# Arduino_DIY.net
KiCad netlist of a schematic drawn in Altium Designer
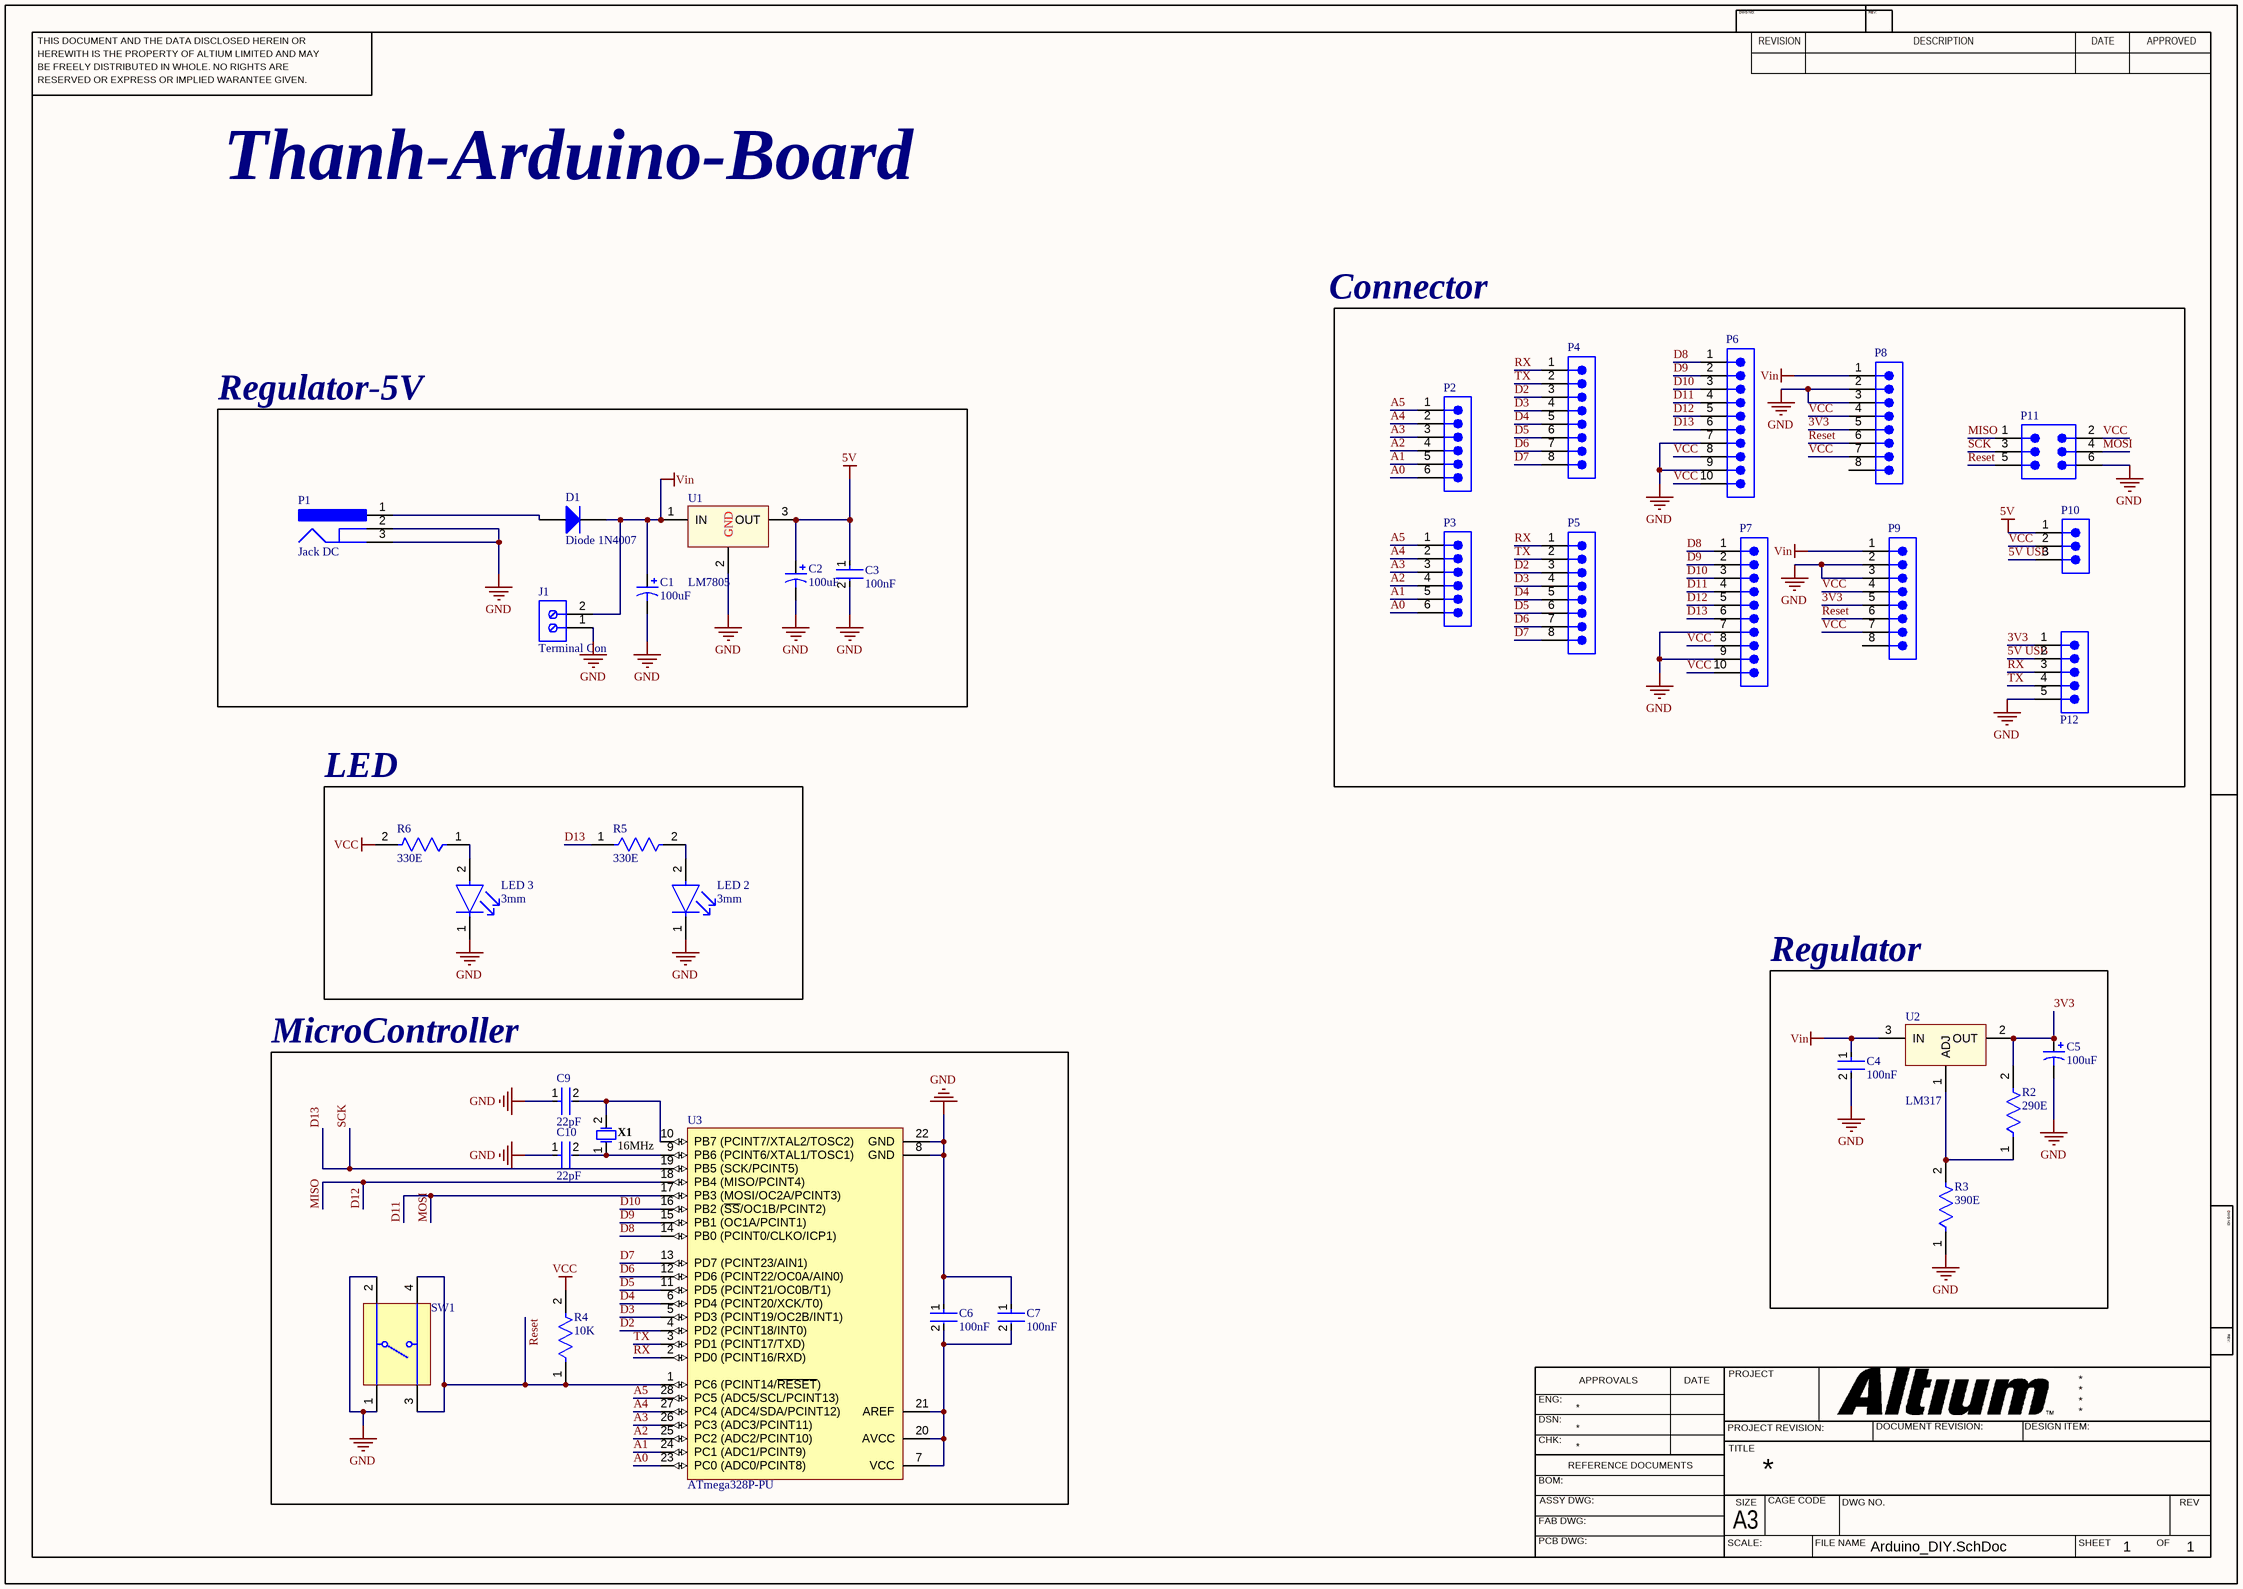
[diagram p0: Arduino_DIY.SchDoc]

(export (version "E")
  (design (tool "Eeschema 10.0.6"))
  (components
    (comp (ref "C1")
      (value "100uF")
      (footprint "CAP_D6.3")
      (description "Polarized Capacitor (Axial)")
      (fields (field (name "PUBLISHER") "Altium Limited"))
      (libsource (lib "CHN_Library") (part "Cap Pol 6mm"))
    )
    (comp (ref "C2")
      (value "100uF")
      (footprint "CAP_D6.3")
      (description "Polarized Capacitor (Axial)")
      (fields (field (name "PUBLISHER") "Altium Limited"))
      (libsource (lib "CHN_Library") (part "Cap Pol 6mm"))
    )
    (comp (ref "C3")
      (value "100nF")
      (footprint "FP-RCE0DB-MFG")
      (description "Cap Ceramic 220pF 50V C0G ±5% Radial 2.5mm +125°C Ammo Pack")
      (fields (field (name "TOLERANCE") "5%") (field (name "VOLTAGE") "50V"))
      (libsource (lib "Altium Content Vault") (part "b4654b650e69147ec39a6b967a45e02"))
    )
    (comp (ref "C4")
      (value "100nF")
      (footprint "FP-RCE0DB-MFG")
      (description "Cap Ceramic 220pF 50V C0G ±5% Radial 2.5mm +125°C Ammo Pack")
      (fields (field (name "TOLERANCE") "5%") (field (name "VOLTAGE") "50V"))
      (libsource (lib "Altium Content Vault") (part "b4654b650e69147ec39a6b967a45e02"))
    )
    (comp (ref "C5")
      (value "100uF")
      (footprint "CAP_D6.3")
      (description "Polarized Capacitor (Axial)")
      (fields (field (name "PUBLISHER") "Altium Limited"))
      (libsource (lib "CHN_Library") (part "Cap Pol 6mm"))
    )
    (comp (ref "C6")
      (value "100nF")
      (footprint "FP-RCE0DB-MFG")
      (description "Cap Ceramic 220pF 50V C0G ±5% Radial 2.5mm +125°C Ammo Pack")
      (fields (field (name "TOLERANCE") "5%") (field (name "VOLTAGE") "50V"))
      (libsource (lib "Altium Content Vault") (part "b4654b650e69147ec39a6b967a45e02"))
    )
    (comp (ref "C7")
      (value "100nF")
      (footprint "FP-RCE0DB-MFG")
      (description "Cap Ceramic 220pF 50V C0G ±5% Radial 2.5mm +125°C Ammo Pack")
      (fields (field (name "TOLERANCE") "5%") (field (name "VOLTAGE") "50V"))
      (libsource (lib "Altium Content Vault") (part "b4654b650e69147ec39a6b967a45e02"))
    )
    (comp (ref "C9")
      (value "22pF")
      (footprint "FP-RCE0DB-MFG")
      (description "Cap Ceramic 220pF 50V C0G ±5% Radial 2.5mm +125°C Ammo Pack")
      (fields (field (name "TOLERANCE") "5%") (field (name "VOLTAGE") "50V"))
      (libsource (lib "Altium Content Vault") (part "b4654b650e69147ec39a6b967a45e02"))
    )
    (comp (ref "C10")
      (value "22pF")
      (footprint "FP-RCE0DB-MFG")
      (description "Cap Ceramic 220pF 50V C0G ±5% Radial 2.5mm +125°C Ammo Pack")
      (fields (field (name "TOLERANCE") "5%") (field (name "VOLTAGE") "50V"))
      (libsource (lib "Altium Content Vault") (part "b4654b650e69147ec39a6b967a45e02"))
    )
    (comp (ref "D1")
      (value "Diode 1N4007")
      (footprint "DO-41")
      (description "1 Amp General Purpose Rectifier")
      (fields (field (name "PUBLISHER") "Altium Limited"))
      (libsource (lib "Miscellaneous Devices") (part "Diode 1N4007"))
    )
    (comp (ref "J1")
      (value "Terminal Con")
      (footprint "691214110002")
      (fields (field (name "VOLTAGE") "300V"))
      (libsource (lib "Altium Content Vault") (part "TBL - 1R - 02P - Screw"))
    )
    (comp (ref "LED 2")
      (value "3mm")
      (footprint "FP-HLMP-1503-MFG")
      (description "LED GREEN DIFFUSED T-1 T/H")
      (fields (field (name "MANUFACTURER") "Broadcom") (field (name "MANUFACTURER PART NUMBER") "HLMP-1503"))
      (libsource (lib "Altium Content Vault") (part "8706943c75ba83719d021d2fdc84c58"))
    )
    (comp (ref "LED 3")
      (value "3mm")
      (footprint "FP-HLMP-1503-MFG")
      (description "LED GREEN DIFFUSED T-1 T/H")
      (fields (field (name "MANUFACTURER") "Broadcom") (field (name "MANUFACTURER PART NUMBER") "HLMP-1503"))
      (libsource (lib "Altium Content Vault") (part "8706943c75ba83719d021d2fdc84c58"))
    )
    (comp (ref "P1")
      (value "Jack DC")
      (footprint "KYCN-KLDX-0202-A_V")
      (description "DC Power Jack, 24 V, 3.5 A, -25 to 85 degC, 3-Pin THD, RoHS")
      (fields (field (name "MANUFACTURER") "Kycon"))
      (libsource (lib "Altium Content Vault") (part "JACK-2CD3-RN"))
    )
    (comp (ref "P2")
      (value "Header 6")
      (footprint "61300611121")
      (libsource (lib "Altium Content Vault") (part "Header_Male_1R_06P"))
    )
    (comp (ref "P3")
      (value "Header 6")
      (footprint "61300611121")
      (libsource (lib "Altium Content Vault") (part "Header_Male_1R_06P"))
    )
    (comp (ref "P4")
      (value "61300811121")
      (footprint "61300811121")
      (libsource (lib "Altium Content Vault") (part "Header_Male_1R_08P"))
    )
    (comp (ref "P5")
      (value "61300811121")
      (footprint "61300811121")
      (libsource (lib "Altium Content Vault") (part "Header_Male_1R_08P"))
    )
    (comp (ref "P6")
      (value "Header 10")
      (footprint "61301011121")
      (libsource (lib "Altium Content Vault") (part "Header_Male_1R_10P"))
    )
    (comp (ref "P7")
      (value "Header 10")
      (footprint "61301011121")
      (libsource (lib "Altium Content Vault") (part "Header_Male_1R_10P"))
    )
    (comp (ref "P8")
      (value "61300811121")
      (footprint "61300811121")
      (libsource (lib "Altium Content Vault") (part "Header_Male_1R_08P"))
    )
    (comp (ref "P9")
      (value "61300811121")
      (footprint "61300811121")
      (libsource (lib "Altium Content Vault") (part "Header_Male_1R_08P"))
    )
    (comp (ref "P10")
      (value "61300311121")
      (footprint "61300311121")
      (libsource (lib "Altium Content Vault") (part "Header_Male_1R_03P"))
    )
    (comp (ref "P11")
      (value "61300621121")
      (footprint "61300621121")
      (libsource (lib "Altium Content Vault") (part "Header_Male_2R_06P"))
    )
    (comp (ref "P12")
      (value "61300511121")
      (footprint "61300511121")
      (libsource (lib "Altium Content Vault") (part "Header_Male_1R_05P"))
    )
    (comp (ref "R2")
      (value "290E")
      (footprint "FP-MRS25-MFG")
      (description "RES 1K OHM 0.6W 1% AXIAL")
      (fields (field (name "TOLERANCE") "1%"))
      (libsource (lib "Altium Content Vault") (part "1029c3af85768c4190bb7ad29bc67b5"))
    )
    (comp (ref "R3")
      (value "390E")
      (footprint "FP-MRS25-MFG")
      (description "RES 1K OHM 0.6W 1% AXIAL")
      (fields (field (name "TOLERANCE") "1%"))
      (libsource (lib "Altium Content Vault") (part "1029c3af85768c4190bb7ad29bc67b5"))
    )
    (comp (ref "R4")
      (value "10K")
      (footprint "FP-MRS25-MFG")
      (description "RES 1K OHM 0.6W 1% AXIAL")
      (fields (field (name "TOLERANCE") "1%"))
      (libsource (lib "Altium Content Vault") (part "1029c3af85768c4190bb7ad29bc67b5"))
    )
    (comp (ref "R5")
      (value "330E")
      (footprint "FP-MRS25-MFG")
      (description "RES 1K OHM 0.6W 1% AXIAL")
      (fields (field (name "TOLERANCE") "1%"))
      (libsource (lib "Altium Content Vault") (part "1029c3af85768c4190bb7ad29bc67b5"))
    )
    (comp (ref "R6")
      (value "330E")
      (footprint "FP-MRS25-MFG")
      (description "RES 1K OHM 0.6W 1% AXIAL")
      (fields (field (name "TOLERANCE") "1%"))
      (libsource (lib "Altium Content Vault") (part "1029c3af85768c4190bb7ad29bc67b5"))
    )
    (comp (ref "SW1")
      (value "Button")
      (footprint "TECO-1825910-6_V")
      (description "Tact Switch, SPST-NO, 0.05 A, -35 to 85 degC, 4-Pin THD, RoHS, Bulk")
      (fields (field (name "PART NO") "1825910-6") (field (name "MANUFACTURER") "TE Connectivity"))
      (libsource (lib "Altium Content Vault") (part "SW-SPST-4_A"))
    )
    (comp (ref "U1")
      (value "LM7805")
      (footprint "QTO-220")
      (description "On ap +, from + 5 to + 24VDC")
      (libsource (lib "CHN_Library") (part "LM78xx"))
    )
    (comp (ref "U2")
      (value "LM317")
      (footprint "QTO-220")
      (description "Adj Voltage +1.2 -> +37V")
      (libsource (lib "CHN_Library") (part "LM317"))
    )
    (comp (ref "U3")
      (value "ATmega328P-PU")
      (footprint "28P3")
      (libsource (lib "Altium Content Vault") (part "MC-8B-ATM48-IL28"))
    )
    (comp (ref "X1")
      (value "16MHz")
      (footprint "FOX-FOXSLF080-20")
      (description "Resistance Weld Thru-Hole Crystal, 8 MHz, -20 to 70 degC, 2-Pin THD, RoHS, Bulk")
      (libsource (lib "Altium Content Vault") (part "XTAL-1-2-2"))
    )
  )
  (nets
    (net (code "1") (name "/3V3") (class "Default")
      (node (ref "C5") (pin "1") (pinfunction "1_1") (pintype "passive"))
      (node (ref "P12") (pin "1") (pinfunction "1_1") (pintype "passive"))
      (node (ref "P8") (pin "5") (pinfunction "5_5") (pintype "passive"))
      (node (ref "P9") (pin "5") (pinfunction "5_5") (pintype "passive"))
      (node (ref "R2") (pin "2") (pinfunction "2_2") (pintype "passive"))
      (node (ref "U2") (pin "2") (pinfunction "OUT_2") (pintype "passive"))
    )
    (net (code "2") (name "/5V USB") (class "Default")
      (node (ref "P10") (pin "3") (pinfunction "3_3") (pintype "passive"))
      (node (ref "P12") (pin "2") (pinfunction "2_2") (pintype "passive"))
    )
    (net (code "3") (name "/A0") (class "Default")
      (node (ref "P2") (pin "6") (pinfunction "6_6") (pintype "passive"))
      (node (ref "P3") (pin "6") (pinfunction "6_6") (pintype "passive"))
      (node (ref "U3") (pin "23") (pinfunction "PC0_(ADC0/PCINT8)_23") (pintype "bidirectional"))
    )
    (net (code "4") (name "/A1") (class "Default")
      (node (ref "P2") (pin "5") (pinfunction "5_5") (pintype "passive"))
      (node (ref "P3") (pin "5") (pinfunction "5_5") (pintype "passive"))
      (node (ref "U3") (pin "24") (pinfunction "PC1_(ADC1/PCINT9)_24") (pintype "bidirectional"))
    )
    (net (code "5") (name "/A2") (class "Default")
      (node (ref "P2") (pin "4") (pinfunction "4_4") (pintype "passive"))
      (node (ref "P3") (pin "4") (pinfunction "4_4") (pintype "passive"))
      (node (ref "U3") (pin "25") (pinfunction "PC2_(ADC2/PCINT10)_25") (pintype "bidirectional"))
    )
    (net (code "6") (name "/A3") (class "Default")
      (node (ref "P2") (pin "3") (pinfunction "3_3") (pintype "passive"))
      (node (ref "P3") (pin "3") (pinfunction "3_3") (pintype "passive"))
      (node (ref "U3") (pin "26") (pinfunction "PC3_(ADC3/PCINT11)_26") (pintype "bidirectional"))
    )
    (net (code "7") (name "/A4") (class "Default")
      (node (ref "P2") (pin "2") (pinfunction "2_2") (pintype "passive"))
      (node (ref "P3") (pin "2") (pinfunction "2_2") (pintype "passive"))
      (node (ref "U3") (pin "27") (pinfunction "PC4_(ADC4/SDA/PCINT12)_27") (pintype "bidirectional"))
    )
    (net (code "8") (name "/A5") (class "Default")
      (node (ref "P2") (pin "1") (pinfunction "1_1") (pintype "passive"))
      (node (ref "P3") (pin "1") (pinfunction "1_1") (pintype "passive"))
      (node (ref "U3") (pin "28") (pinfunction "PC5_(ADC5/SCL/PCINT13)_28") (pintype "bidirectional"))
    )
    (net (code "9") (name "/D2") (class "Default")
      (node (ref "P4") (pin "3") (pinfunction "3_3") (pintype "passive"))
      (node (ref "P5") (pin "3") (pinfunction "3_3") (pintype "passive"))
      (node (ref "U3") (pin "4") (pinfunction "PD2_(PCINT18/INT0)_4") (pintype "bidirectional"))
    )
    (net (code "10") (name "/D3") (class "Default")
      (node (ref "P4") (pin "4") (pinfunction "4_4") (pintype "passive"))
      (node (ref "P5") (pin "4") (pinfunction "4_4") (pintype "passive"))
      (node (ref "U3") (pin "5") (pinfunction "PD3_(PCINT19/OC2B/INT1)_5") (pintype "bidirectional"))
    )
    (net (code "11") (name "/D4") (class "Default")
      (node (ref "P4") (pin "5") (pinfunction "5_5") (pintype "passive"))
      (node (ref "P5") (pin "5") (pinfunction "5_5") (pintype "passive"))
      (node (ref "U3") (pin "6") (pinfunction "PD4_(PCINT20/XCK/T0)_6") (pintype "bidirectional"))
    )
    (net (code "12") (name "/D5") (class "Default")
      (node (ref "P4") (pin "6") (pinfunction "6_6") (pintype "passive"))
      (node (ref "P5") (pin "6") (pinfunction "6_6") (pintype "passive"))
      (node (ref "U3") (pin "11") (pinfunction "PD5_(PCINT21/OC0B/T1)_11") (pintype "bidirectional"))
    )
    (net (code "13") (name "/D6") (class "Default")
      (node (ref "P4") (pin "7") (pinfunction "7_7") (pintype "passive"))
      (node (ref "P5") (pin "7") (pinfunction "7_7") (pintype "passive"))
      (node (ref "U3") (pin "12") (pinfunction "PD6_(PCINT22/OC0A/AIN0)_12") (pintype "bidirectional"))
    )
    (net (code "14") (name "/D7") (class "Default")
      (node (ref "P4") (pin "8") (pinfunction "8_8") (pintype "passive"))
      (node (ref "P5") (pin "8") (pinfunction "8_8") (pintype "passive"))
      (node (ref "U3") (pin "13") (pinfunction "PD7_(PCINT23/AIN1)_13") (pintype "bidirectional"))
    )
    (net (code "15") (name "/D8") (class "Default")
      (node (ref "P6") (pin "1") (pinfunction "1_1") (pintype "passive"))
      (node (ref "P7") (pin "1") (pinfunction "1_1") (pintype "passive"))
      (node (ref "U3") (pin "14") (pinfunction "PB0_(PCINT0/CLKO/ICP1)_14") (pintype "bidirectional"))
    )
    (net (code "16") (name "/D9") (class "Default")
      (node (ref "P6") (pin "2") (pinfunction "2_2") (pintype "passive"))
      (node (ref "P7") (pin "2") (pinfunction "2_2") (pintype "passive"))
      (node (ref "U3") (pin "15") (pinfunction "PB1_(OC1A/PCINT1)_15") (pintype "bidirectional"))
    )
    (net (code "17") (name "/D10") (class "Default")
      (node (ref "P6") (pin "3") (pinfunction "3_3") (pintype "passive"))
      (node (ref "P7") (pin "3") (pinfunction "3_3") (pintype "passive"))
      (node (ref "U3") (pin "16") (pinfunction "PB2_(~{SS}/OC1B/PCINT2)_16") (pintype "bidirectional"))
    )
    (net (code "18") (name "/D11") (class "Default")
      (node (ref "P11") (pin "4") (pinfunction "4_4") (pintype "passive"))
      (node (ref "P6") (pin "4") (pinfunction "4_4") (pintype "passive"))
      (node (ref "P7") (pin "4") (pinfunction "4_4") (pintype "passive"))
      (node (ref "U3") (pin "17") (pinfunction "PB3_(MOSI/OC2A/PCINT3)_17") (pintype "bidirectional"))
    )
    (net (code "19") (name "/D12") (class "Default")
      (node (ref "P11") (pin "1") (pinfunction "1_1") (pintype "passive"))
      (node (ref "P6") (pin "5") (pinfunction "5_5") (pintype "passive"))
      (node (ref "P7") (pin "5") (pinfunction "5_5") (pintype "passive"))
      (node (ref "U3") (pin "18") (pinfunction "PB4_(MISO/PCINT4)_18") (pintype "bidirectional"))
    )
    (net (code "20") (name "/D13") (class "Default")
      (node (ref "P11") (pin "3") (pinfunction "3_3") (pintype "passive"))
      (node (ref "P6") (pin "6") (pinfunction "6_6") (pintype "passive"))
      (node (ref "P7") (pin "6") (pinfunction "6_6") (pintype "passive"))
      (node (ref "R5") (pin "1") (pinfunction "1_1") (pintype "passive"))
      (node (ref "U3") (pin "19") (pinfunction "PB5_(SCK/PCINT5)_19") (pintype "bidirectional"))
    )
    (net (code "21") (name "/RX") (class "Default")
      (node (ref "P12") (pin "3") (pinfunction "3_3") (pintype "passive"))
      (node (ref "P4") (pin "1") (pinfunction "1_1") (pintype "passive"))
      (node (ref "P5") (pin "1") (pinfunction "1_1") (pintype "passive"))
      (node (ref "U3") (pin "2") (pinfunction "PD0_(PCINT16/RXD)_2") (pintype "bidirectional"))
    )
    (net (code "22") (name "/Reset") (class "Default")
      (node (ref "P11") (pin "5") (pinfunction "5_5") (pintype "passive"))
      (node (ref "P8") (pin "6") (pinfunction "6_6") (pintype "passive"))
      (node (ref "P9") (pin "6") (pinfunction "6_6") (pintype "passive"))
      (node (ref "R4") (pin "1") (pinfunction "1_1") (pintype "passive"))
      (node (ref "SW1") (pin "3") (pinfunction "3_3") (pintype "passive"))
      (node (ref "SW1") (pin "4") (pinfunction "4_4") (pintype "passive"))
      (node (ref "U3") (pin "1") (pinfunction "PC6_(PCINT14/~{RESET})_1") (pintype "bidirectional"))
    )
    (net (code "23") (name "/TX") (class "Default")
      (node (ref "P12") (pin "4") (pinfunction "4_4") (pintype "passive"))
      (node (ref "P4") (pin "2") (pinfunction "2_2") (pintype "passive"))
      (node (ref "P5") (pin "2") (pinfunction "2_2") (pintype "passive"))
      (node (ref "U3") (pin "3") (pinfunction "PD1_(PCINT17/TXD)_3") (pintype "bidirectional"))
    )
    (net (code "24") (name "5V") (class "Default")
      (node (ref "C2") (pin "1") (pinfunction "1_1") (pintype "passive"))
      (node (ref "C3") (pin "1") (pinfunction "1_1") (pintype "passive"))
      (node (ref "P10") (pin "1") (pinfunction "1_1") (pintype "passive"))
      (node (ref "U1") (pin "3") (pinfunction "OUT_3") (pintype "passive"))
    )
    (net (code "25") (name "GND") (class "Default")
      (node (ref "C1") (pin "2") (pinfunction "2_2") (pintype "passive"))
      (node (ref "C10") (pin "1") (pinfunction "1_1") (pintype "passive"))
      (node (ref "C2") (pin "2") (pinfunction "2_2") (pintype "passive"))
      (node (ref "C3") (pin "2") (pinfunction "2_2") (pintype "passive"))
      (node (ref "C4") (pin "2") (pinfunction "2_2") (pintype "passive"))
      (node (ref "C5") (pin "2") (pinfunction "2_2") (pintype "passive"))
      (node (ref "C6") (pin "1") (pinfunction "1_1") (pintype "passive"))
      (node (ref "C7") (pin "1") (pinfunction "1_1") (pintype "passive"))
      (node (ref "C9") (pin "1") (pinfunction "1_1") (pintype "passive"))
      (node (ref "J1") (pin "1") (pinfunction "1_1") (pintype "passive"))
      (node (ref "LED 2") (pin "1") (pinfunction "C_1") (pintype "passive"))
      (node (ref "LED 3") (pin "1") (pinfunction "C_1") (pintype "passive"))
      (node (ref "P1") (pin "2") (pinfunction "2_2") (pintype "passive"))
      (node (ref "P1") (pin "3") (pinfunction "3_3") (pintype "passive"))
      (node (ref "P11") (pin "6") (pinfunction "6_6") (pintype "passive"))
      (node (ref "P12") (pin "5") (pinfunction "5_5") (pintype "passive"))
      (node (ref "P6") (pin "7") (pinfunction "7_7") (pintype "passive"))
      (node (ref "P6") (pin "9") (pinfunction "9_9") (pintype "passive"))
      (node (ref "P7") (pin "7") (pinfunction "7_7") (pintype "passive"))
      (node (ref "P7") (pin "9") (pinfunction "9_9") (pintype "passive"))
      (node (ref "P8") (pin "2") (pinfunction "2_2") (pintype "passive"))
      (node (ref "P8") (pin "3") (pinfunction "3_3") (pintype "passive"))
      (node (ref "P9") (pin "2") (pinfunction "2_2") (pintype "passive"))
      (node (ref "P9") (pin "3") (pinfunction "3_3") (pintype "passive"))
      (node (ref "R3") (pin "1") (pinfunction "1_1") (pintype "passive"))
      (node (ref "SW1") (pin "1") (pinfunction "1_1") (pintype "passive"))
      (node (ref "SW1") (pin "2") (pinfunction "2_2") (pintype "passive"))
      (node (ref "U1") (pin "2") (pinfunction "GND_2") (pintype "passive"))
      (node (ref "U3") (pin "22") (pinfunction "GND_22") (pintype "power_in"))
      (node (ref "U3") (pin "8") (pinfunction "GND_8") (pintype "power_in"))
    )
    (net (code "26") (name "Net-(D1-A)") (class "Default")
      (node (ref "D1") (pin "1") (pinfunction "A_1") (pintype "passive"))
      (node (ref "P1") (pin "1") (pinfunction "1_1") (pintype "passive"))
    )
    (net (code "27") (name "Net-(LED 2-A)") (class "Default")
      (node (ref "LED 2") (pin "2") (pinfunction "A_2") (pintype "passive"))
      (node (ref "R5") (pin "2") (pinfunction "2_2") (pintype "passive"))
    )
    (net (code "28") (name "Net-(LED 3-A)") (class "Default")
      (node (ref "LED 3") (pin "2") (pinfunction "A_2") (pintype "passive"))
      (node (ref "R6") (pin "1") (pinfunction "1_1") (pintype "passive"))
    )
    (net (code "29") (name "Net-(U2-ADJ)") (class "Default")
      (node (ref "R2") (pin "1") (pinfunction "1_1") (pintype "passive"))
      (node (ref "R3") (pin "2") (pinfunction "2_2") (pintype "passive"))
      (node (ref "U2") (pin "1") (pinfunction "ADJ_1") (pintype "passive"))
    )
    (net (code "30") (name "Net-(U3-AREF)") (class "Default")
      (node (ref "C6") (pin "2") (pinfunction "2_2") (pintype "passive"))
      (node (ref "C7") (pin "2") (pinfunction "2_2") (pintype "passive"))
      (node (ref "U3") (pin "20") (pinfunction "AVCC_20") (pintype "power_in"))
      (node (ref "U3") (pin "21") (pinfunction "AREF_21") (pintype "power_in"))
      (node (ref "U3") (pin "7") (pinfunction "VCC_7") (pintype "power_in"))
    )
    (net (code "31") (name "Net-(U3-PB6_(PCINT6{slash}XTAL1{slash}TOSC1))") (class "Default")
      (node (ref "C10") (pin "2") (pinfunction "2_2") (pintype "passive"))
      (node (ref "U3") (pin "9") (pinfunction "PB6_(PCINT6/XTAL1/TOSC1)_9") (pintype "bidirectional"))
      (node (ref "X1") (pin "1") (pinfunction "1_1") (pintype "passive"))
    )
    (net (code "32") (name "Net-(U3-PB7_(PCINT7{slash}XTAL2{slash}TOSC2))") (class "Default")
      (node (ref "C9") (pin "2") (pinfunction "2_2") (pintype "passive"))
      (node (ref "U3") (pin "10") (pinfunction "PB7_(PCINT7/XTAL2/TOSC2)_10") (pintype "bidirectional"))
      (node (ref "X1") (pin "2") (pinfunction "2_2") (pintype "passive"))
    )
    (net (code "33") (name "VCC") (class "Default")
      (node (ref "P10") (pin "2") (pinfunction "2_2") (pintype "passive"))
      (node (ref "P11") (pin "2") (pinfunction "2_2") (pintype "passive"))
      (node (ref "P6") (pin "10") (pinfunction "10_10") (pintype "passive"))
      (node (ref "P6") (pin "8") (pinfunction "8_8") (pintype "passive"))
      (node (ref "P7") (pin "10") (pinfunction "10_10") (pintype "passive"))
      (node (ref "P7") (pin "8") (pinfunction "8_8") (pintype "passive"))
      (node (ref "P8") (pin "4") (pinfunction "4_4") (pintype "passive"))
      (node (ref "P8") (pin "7") (pinfunction "7_7") (pintype "passive"))
      (node (ref "P9") (pin "4") (pinfunction "4_4") (pintype "passive"))
      (node (ref "P9") (pin "7") (pinfunction "7_7") (pintype "passive"))
      (node (ref "R4") (pin "2") (pinfunction "2_2") (pintype "passive"))
      (node (ref "R6") (pin "2") (pinfunction "2_2") (pintype "passive"))
    )
    (net (code "34") (name "Vin") (class "Default")
      (node (ref "C1") (pin "1") (pinfunction "1_1") (pintype "passive"))
      (node (ref "C4") (pin "1") (pinfunction "1_1") (pintype "passive"))
      (node (ref "D1") (pin "2") (pinfunction "K_2") (pintype "passive"))
      (node (ref "J1") (pin "2") (pinfunction "2_2") (pintype "passive"))
      (node (ref "P8") (pin "1") (pinfunction "1_1") (pintype "passive"))
      (node (ref "P9") (pin "1") (pinfunction "1_1") (pintype "passive"))
      (node (ref "U1") (pin "1") (pinfunction "IN_1") (pintype "passive"))
      (node (ref "U2") (pin "3") (pinfunction "IN_3") (pintype "passive"))
    )
    (net (code "35") (name "unconnected-(P8-Pad8)") (class "Default")
      (node (ref "P8") (pin "8") (pinfunction "8_8") (pintype "passive"))
    )
    (net (code "36") (name "unconnected-(P9-Pad8)") (class "Default")
      (node (ref "P9") (pin "8") (pinfunction "8_8") (pintype "passive"))
    )
  )
)
